# ST1S40IDR.net
KiCad netlist of a schematic drawn in Altium Designer
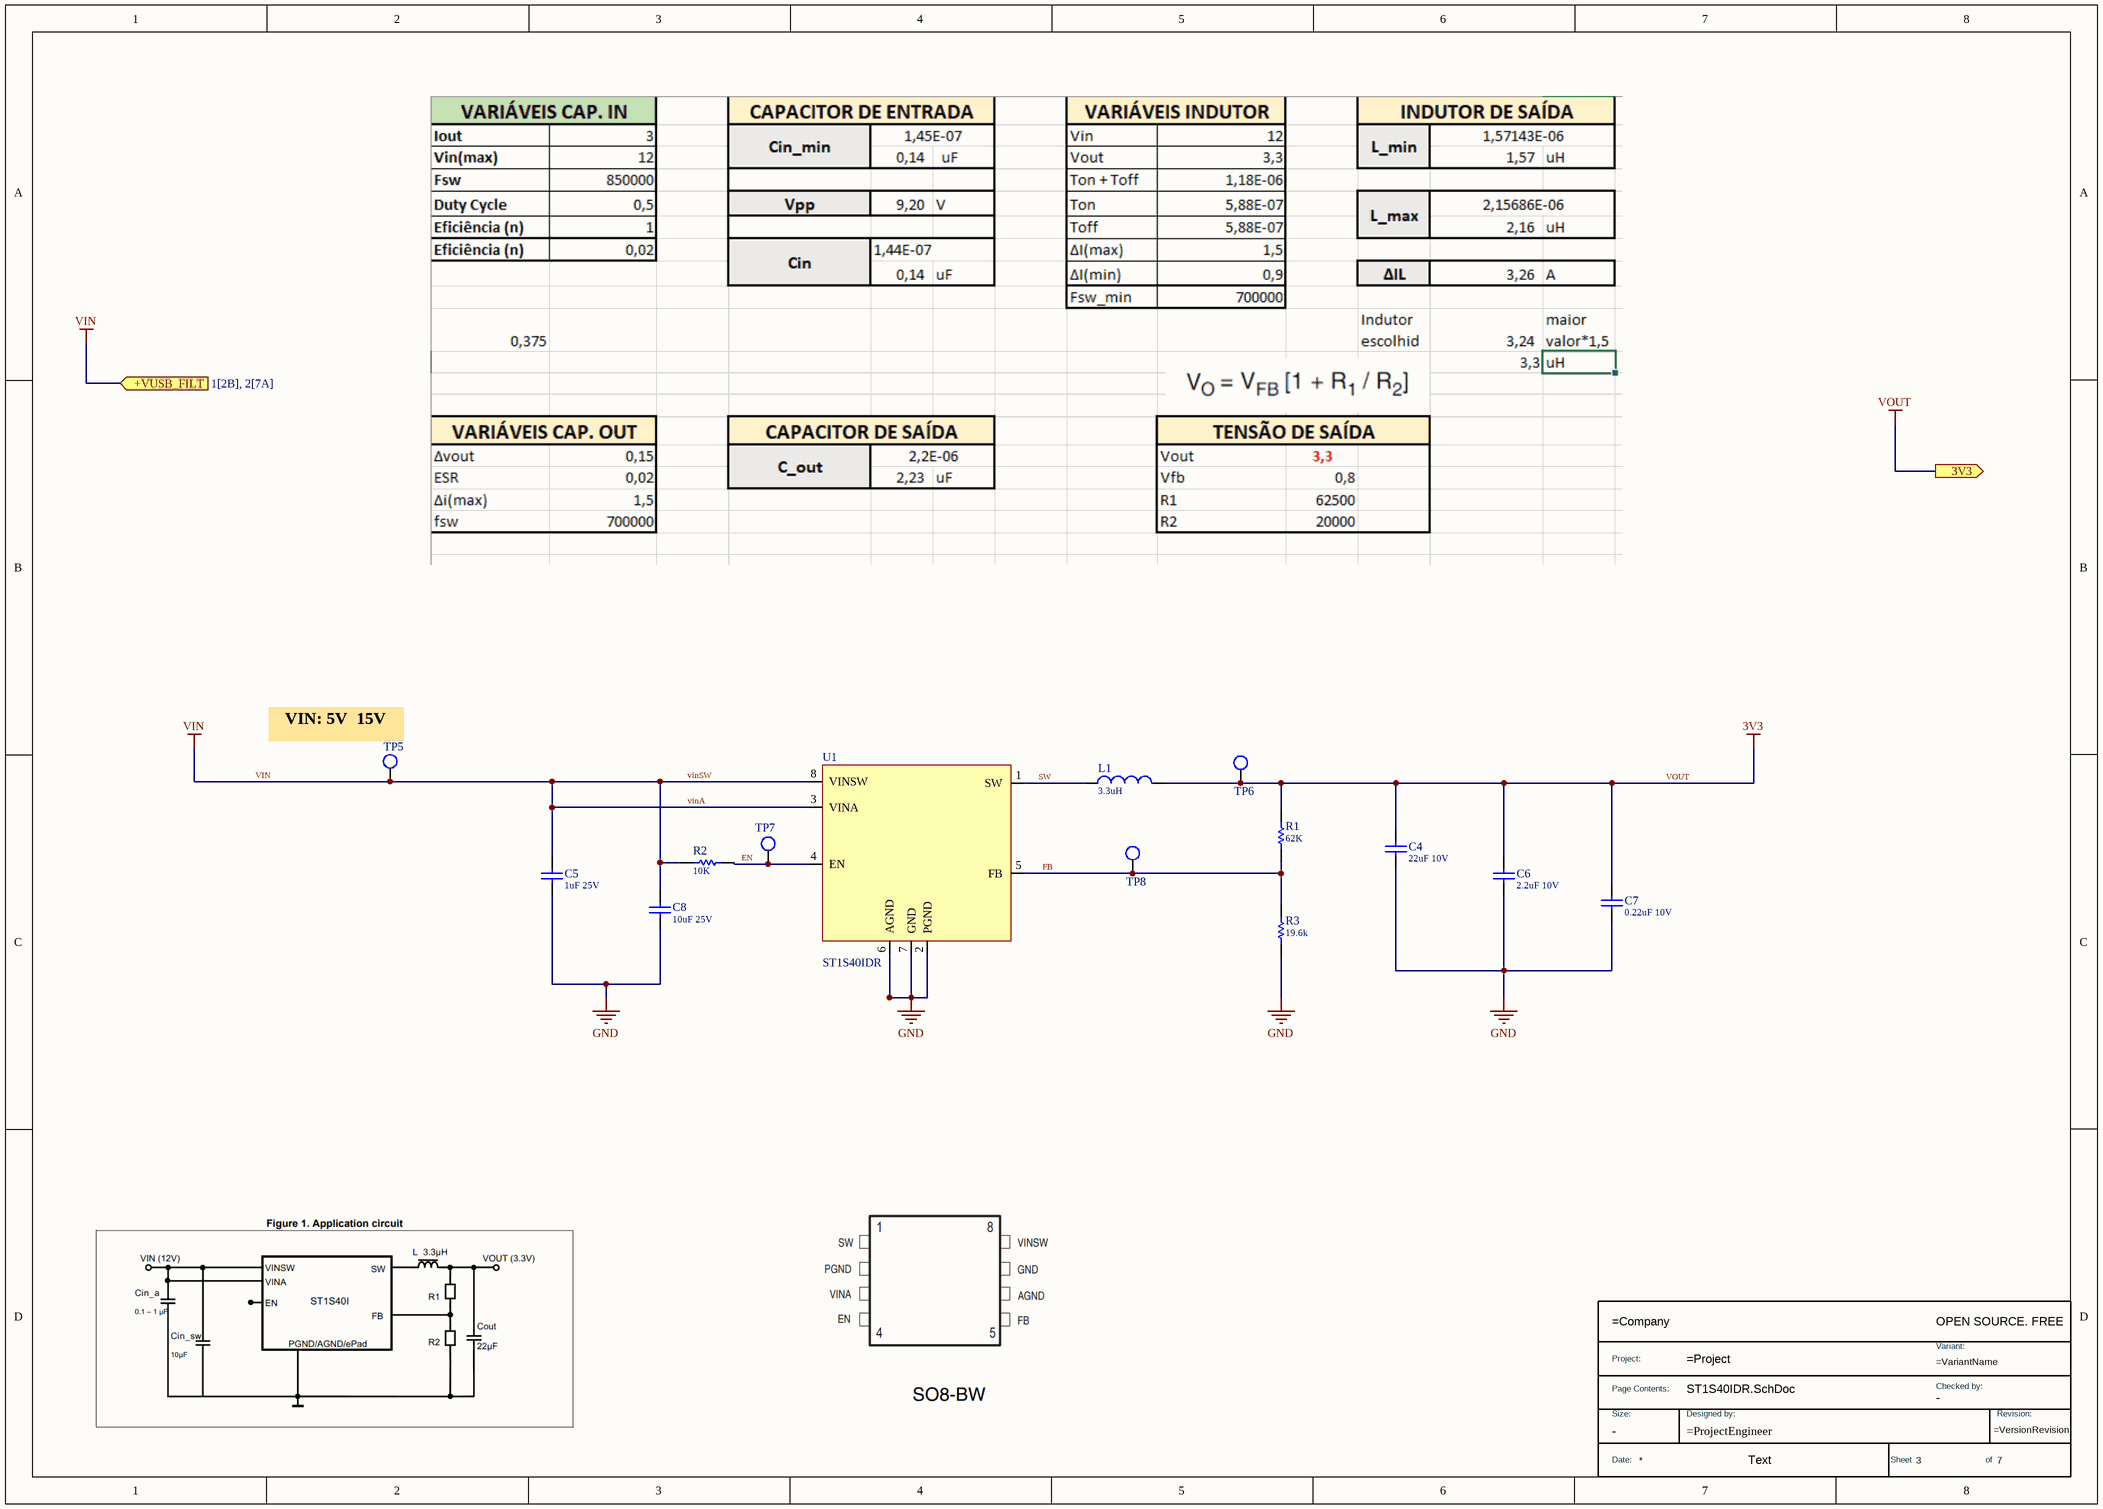
[diagram p0: ST1S40IDR.SchDoc]

(export (version "E")
  (design (tool "Eeschema 10.0.6"))
  (components
    (comp (ref "C4")
      (value "CL21A226MPQNNNE")
      (footprint "0805")
      (description "CAP CER 22UF 10V X5R 0805")
      (fields (field (name "MANUFACTURER") "Samsung Electro-Mechanics") (field (name "VALOR") "22uF 10V"))
      (libsource (lib "OBDH_Ed02") (part "CL21A226MPQNNNE"))
    )
    (comp (ref "C5")
      (value "CL21B105KAFNNNE")
      (footprint "CAP_0805")
      (description "CAP CER 1UF 25V X7R 0805")
      (fields (field (name "MANUFACTURER") "Samsung Electro-Mechanics") (field (name "VALOR") "1uF 25V"))
      (libsource (lib "OBDH_Ed02") (part "CL21B105KAFNNNE"))
    )
    (comp (ref "C6")
      (value "CL21B225KAFNNNE")
      (footprint "0805")
      (description "CAP CER 2.2UF 10V X5R 0805")
      (fields (field (name "MANUFACTURER") "Samsung Electro-Mechanics") (field (name "VALOR") "2.2uF 10V"))
      (libsource (lib "OBDH_Ed02") (part "CL21B225KAFNNNE"))
    )
    (comp (ref "C7")
      (value "CC0805KRX7R6BB224")
      (footprint "0805")
      (description "CAP CER 0.22uF 10V X5R 0805")
      (fields (field (name "MANUFACTURER") "YAGEO") (field (name "VALOR") "0.22uF 10V"))
      (libsource (lib "OBDH_Ed02") (part "CC0805KRX7R6BB224"))
    )
    (comp (ref "C8")
      (value "CL21A106KAYNNNE")
      (footprint "CAP_0805")
      (description "CAP CER 10UF 25V X5R 0805")
      (fields (field (name "MANUFACTURER") "Samsung Electro-Mechanics") (field (name "VALOR") "10uF 25V"))
      (libsource (lib "OBDH_Ed02") (part "CL21A106KAYNNNE"))
    )
    (comp (ref "L1")
      (value "3.3uH")
      (footprint "IND_6.1-4")
      (description "FIXED IND 3.3UH 4.2A 35.1MOHM SM")
      (fields (field (name "MANUFACTURER PART NUMBER") "VLS5045EX-3R3N-H"))
      (libsource (lib "OBDH_Ed02") (part "VLS5045EX-3R3N-H"))
    )
    (comp (ref "R1")
      (value "CRCW080562K0JNEA")
      (footprint "RES_0805")
      (description "RES SMD 62K OHM 5% 1/8W 0805")
      (fields (field (name "MANUFACTURER") "YAGEO") (field (name "VALOR") "62K"))
      (libsource (lib "OBDH_Ed02") (part "CRCW080562K0JNEA"))
    )
    (comp (ref "R2")
      (value "AF0805JR-0710KL")
      (footprint "RES_0805")
      (description "RES SMD 10K OHM 5% 1/8W 0805")
      (fields (field (name "MANUFACTURER") "YAGEO") (field (name "VALOR") "10K"))
      (libsource (lib "OBDH_Ed02") (part "AF0805JR-0710KL"))
    )
    (comp (ref "R3")
      (value "RT0805BRD0719K6L")
      (footprint "RES_0805")
      (description "RES SMD 19.6K OHM 5% 1/8W 0805")
      (fields (field (name "MANUFACTURER") "YAGEO") (field (name "VALOR") "19.6k"))
      (libsource (lib "OBDH_Ed02") (part "RT0805BRD0719K6L"))
    )
    (comp (ref "TP5")
      (value "TEST_POINT_1.5MM")
      (footprint "TESTPOINT_1.5MM")
      (description "TEST_POINT")
      (libsource (lib "OBDH_Ed02") (part "TEST_POINT_1.5MM"))
    )
    (comp (ref "TP6")
      (value "TEST_POINT_1.5MM")
      (footprint "TESTPOINT_1.5MM")
      (description "TEST_POINT")
      (libsource (lib "OBDH_Ed02") (part "TEST_POINT_1.5MM"))
    )
    (comp (ref "TP7")
      (value "TEST_POINT_1.5MM")
      (footprint "TESTPOINT_1.5MM")
      (description "TEST_POINT")
      (libsource (lib "OBDH_Ed02") (part "TEST_POINT_1.5MM"))
    )
    (comp (ref "TP8")
      (value "TEST_POINT_1.5MM")
      (footprint "TESTPOINT_1.5MM")
      (description "TEST_POINT")
      (libsource (lib "OBDH_Ed02") (part "TEST_POINT_1.5MM"))
    )
    (comp (ref "U1")
      (value "ST1S40IDR")
      (footprint "SO8-BW")
      (description "IC REG BUCK ADJUSTABLE 3A 8SO")
      (libsource (lib "OBDH_Ed02") (part "ST1S40IDR"))
    )
  )
  (nets
    (net (code "1") (name "/EN") (class "Default")
      (node (ref "R2") (pin "2") (pinfunction "2_2") (pintype "passive"))
      (node (ref "TP7") (pin "1") (pinfunction "1_1") (pintype "passive"))
      (node (ref "U1") (pin "4") (pinfunction "EN_4") (pintype "passive"))
    )
    (net (code "2") (name "/FB") (class "Default")
      (node (ref "R1") (pin "1") (pinfunction "1_1") (pintype "passive"))
      (node (ref "R3") (pin "2") (pinfunction "2_2") (pintype "passive"))
      (node (ref "TP8") (pin "1") (pinfunction "1_1") (pintype "passive"))
      (node (ref "U1") (pin "5") (pinfunction "FB_5") (pintype "passive"))
    )
    (net (code "3") (name "/SW") (class "Default")
      (node (ref "L1") (pin "1") (pinfunction "1_1") (pintype "passive"))
      (node (ref "U1") (pin "1") (pinfunction "SW_1") (pintype "passive"))
    )
    (net (code "4") (name "3V3") (class "Default")
      (node (ref "C4") (pin "2") (pinfunction "2_2") (pintype "passive"))
      (node (ref "C6") (pin "2") (pinfunction "2_2") (pintype "passive"))
      (node (ref "C7") (pin "2") (pinfunction "2_2") (pintype "passive"))
      (node (ref "L1") (pin "2") (pinfunction "2_2") (pintype "passive"))
      (node (ref "R1") (pin "2") (pinfunction "2_2") (pintype "passive"))
      (node (ref "TP6") (pin "1") (pinfunction "1_1") (pintype "passive"))
    )
    (net (code "5") (name "GND") (class "Default")
      (node (ref "C4") (pin "1") (pinfunction "1_1") (pintype "passive"))
      (node (ref "C5") (pin "1") (pinfunction "1_1") (pintype "passive"))
      (node (ref "C6") (pin "1") (pinfunction "1_1") (pintype "passive"))
      (node (ref "C7") (pin "1") (pinfunction "1_1") (pintype "passive"))
      (node (ref "C8") (pin "2") (pinfunction "2_2") (pintype "passive"))
      (node (ref "R3") (pin "1") (pinfunction "1_1") (pintype "passive"))
      (node (ref "U1") (pin "2") (pinfunction "PGND_2") (pintype "passive"))
      (node (ref "U1") (pin "6") (pinfunction "AGND_6") (pintype "passive"))
      (node (ref "U1") (pin "7") (pinfunction "GND_7") (pintype "passive"))
    )
    (net (code "6") (name "VIN") (class "Default")
      (node (ref "C5") (pin "2") (pinfunction "2_2") (pintype "passive"))
      (node (ref "C8") (pin "1") (pinfunction "1_1") (pintype "passive"))
      (node (ref "R2") (pin "1") (pinfunction "1_1") (pintype "passive"))
      (node (ref "TP5") (pin "1") (pinfunction "1_1") (pintype "passive"))
      (node (ref "U1") (pin "3") (pinfunction "VINA_3") (pintype "passive"))
      (node (ref "U1") (pin "8") (pinfunction "VINSW_8") (pintype "passive"))
    )
  )
)
